# BRD2_1.net
KiCad netlist of a schematic drawn in Altium Designer
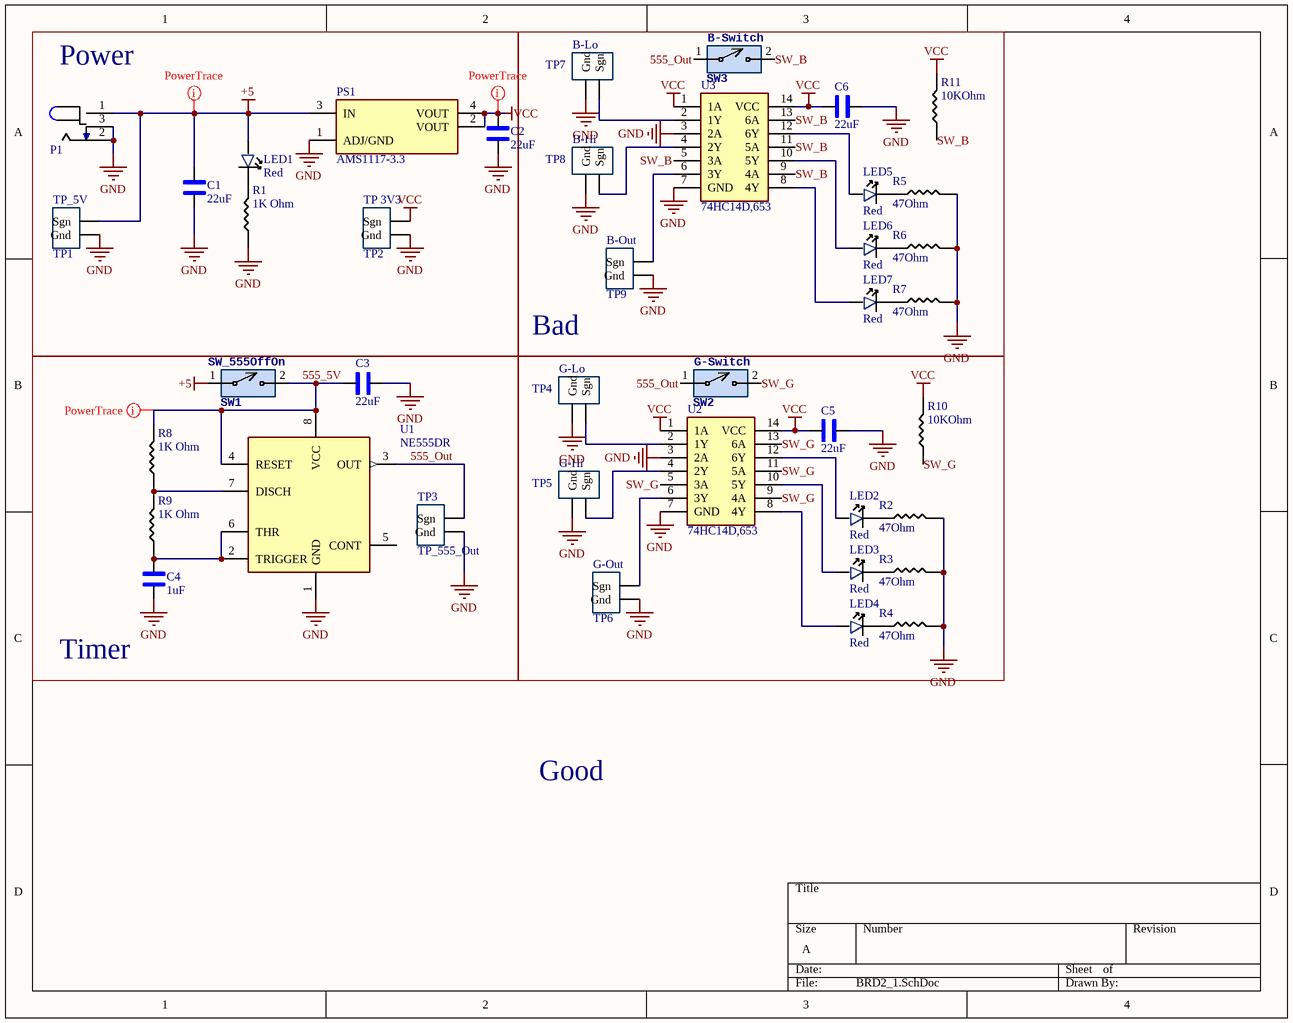
[diagram p0: BRD2_1.SchDoc]

(export (version "E")
  (design (tool "Eeschema 10.0.6"))
  (components
    (comp (ref "C1")
      (value "22uF")
      (footprint "0805_Passive_Capaciitor")
      (description "MULTILAYER CERAMIC CAPACITORS MLCC - SMD/SMT 22UF 25V 0805 ROHS")
      (fields (field (name "MFR PART #") "CL21A226MAQNNNE") (field (name "LCSC PART#") "C45783"))
      (libsource (lib "ECEN5730Lib_JLC_2021_07") (part "C_22uF_0805"))
    )
    (comp (ref "C2")
      (value "22uF")
      (footprint "0805_Passive_Capaciitor")
      (description "MULTILAYER CERAMIC CAPACITORS MLCC - SMD/SMT 22UF 25V 0805 ROHS")
      (fields (field (name "MFR PART #") "CL21A226MAQNNNE") (field (name "LCSC PART#") "C45783"))
      (libsource (lib "ECEN5730Lib_JLC_2021_08") (part "C_22uF_0805"))
    )
    (comp (ref "C3")
      (value "22uF")
      (footprint "0805_Passive_Capaciitor")
      (description "MULTILAYER CERAMIC CAPACITORS MLCC - SMD/SMT 22UF 25V 0805 ROHS")
      (fields (field (name "MFR PART #") "CL21A226MAQNNNE") (field (name "LCSC PART#") "C45783"))
      (libsource (lib "ECEN5730Lib_JLC_2021_07") (part "C_22uF_0805"))
    )
    (comp (ref "C4")
      (value "1uF")
      (footprint "0402_Passive_Capacitor")
      (description "MULTILAYER CERAMIC CAPACITORS MLCC - SMD/SMT 1UF 25V 0402 ROHS")
      (fields (field (name "MFR PART #") "CL05A105KA5NQNC") (field (name "LCSC PART#") "C52923"))
      (libsource (lib "ECEN5730Lib_JLC_2021_07") (part "C_1uF_0402"))
    )
    (comp (ref "C5")
      (value "22uF")
      (footprint "0805_Passive_Capaciitor")
      (description "MULTILAYER CERAMIC CAPACITORS MLCC - SMD/SMT 22UF 25V 0805 ROHS")
      (fields (field (name "MFR PART #") "CL21A226MAQNNNE") (field (name "LCSC PART#") "C45783"))
      (libsource (lib "ECEN5730Lib_JLC_2021_08") (part "C_22uF_0805"))
    )
    (comp (ref "C6")
      (value "22uF")
      (footprint "0805_Passive_Capaciitor")
      (description "MULTILAYER CERAMIC CAPACITORS MLCC - SMD/SMT 22UF 25V 0805 ROHS")
      (fields (field (name "MFR PART #") "CL21A226MAQNNNE") (field (name "LCSC PART#") "C45783"))
      (libsource (lib "ECEN5730Lib_JLC_2021_08") (part "C_22uF_0805"))
    )
    (comp (ref "LED1")
      (value "Red")
      (footprint "LED_0603")
      (description "LIGHT EMITTING DIODES (LED) RED 520~625NM 90~100MCD@20MA TOP VIEW 0603 ROHS")
      (fields (field (name "MFR PART #") "KT-0603R") (field (name "LCSC PART#") "C2286"))
      (libsource (lib "ECEN5730Lib_JLC_2021_07") (part "LED_RED_0603"))
    )
    (comp (ref "LED2")
      (value "Red")
      (footprint "LED_0603")
      (description "LIGHT EMITTING DIODES (LED) RED 520~625NM 90~100MCD@20MA TOP VIEW 0603 ROHS")
      (fields (field (name "MFR PART #") "KT-0603R") (field (name "LCSC PART#") "C2286"))
      (libsource (lib "ECEN5730Lib_JLC_2021_08") (part "LED_RED_0603"))
    )
    (comp (ref "LED3")
      (value "Red")
      (footprint "LED_0603")
      (description "LIGHT EMITTING DIODES (LED) RED 520~625NM 90~100MCD@20MA TOP VIEW 0603 ROHS")
      (fields (field (name "MFR PART #") "KT-0603R") (field (name "LCSC PART#") "C2286"))
      (libsource (lib "ECEN5730Lib_JLC_2021_08") (part "LED_RED_0603"))
    )
    (comp (ref "LED4")
      (value "Red")
      (footprint "LED_0603")
      (description "LIGHT EMITTING DIODES (LED) RED 520~625NM 90~100MCD@20MA TOP VIEW 0603 ROHS")
      (fields (field (name "MFR PART #") "KT-0603R") (field (name "LCSC PART#") "C2286"))
      (libsource (lib "ECEN5730Lib_JLC_2021_08") (part "LED_RED_0603"))
    )
    (comp (ref "LED5")
      (value "Red")
      (footprint "LED_0603")
      (description "LIGHT EMITTING DIODES (LED) RED 520~625NM 90~100MCD@20MA TOP VIEW 0603 ROHS")
      (fields (field (name "MFR PART #") "KT-0603R") (field (name "LCSC PART#") "C2286"))
      (libsource (lib "ECEN5730Lib_JLC_2021_08") (part "LED_RED_0603"))
    )
    (comp (ref "LED6")
      (value "Red")
      (footprint "LED_0603")
      (description "LIGHT EMITTING DIODES (LED) RED 520~625NM 90~100MCD@20MA TOP VIEW 0603 ROHS")
      (fields (field (name "MFR PART #") "KT-0603R") (field (name "LCSC PART#") "C2286"))
      (libsource (lib "ECEN5730Lib_JLC_2021_08") (part "LED_RED_0603"))
    )
    (comp (ref "LED7")
      (value "Red")
      (footprint "LED_0603")
      (description "LIGHT EMITTING DIODES (LED) RED 520~625NM 90~100MCD@20MA TOP VIEW 0603 ROHS")
      (fields (field (name "MFR PART #") "KT-0603R") (field (name "LCSC PART#") "C2286"))
      (libsource (lib "ECEN5730Lib_JLC_2021_08") (part "LED_RED_0603"))
    )
    (comp (ref "P1")
      (value "Power Jack")
      (footprint "Power_Jack")
      (description "Power Barrel Connector Jack 2.10mm ID (0.083\"), 5.50mm OD (0.217\") Through Hole, Right Angle")
      (fields (field (name "DIGIKEY PART") "CP-102A-ND") (field (name "LCSC PART#") "C136744"))
      (libsource (lib "ECEN5730Lib_JLC_2021_07") (part "P_Power Jack"))
    )
    (comp (ref "PS1")
      (value "AMS1117-3.3")
      (footprint "LDO")
      (description "LOW DROPOUT REGULATORS(LDO) POSITIVE FIXED 1.3V @ 800MA 15V 3.3V 1A SOT-223 ROHS")
      (fields (field (name "LCSC PART#") "C6186"))
      (libsource (lib "ECEN5730Lib_JLC_2021_08") (part "PS_AMS_LDO_3v3"))
    )
    (comp (ref "R1")
      (value "1K Ohm")
      (footprint "0402_Passive_Resistor")
      (description "1 kOhms chip resistor SURFACE MOUNT 1KOHMS ±1% 1/16W 0402 ROHS")
      (fields (field (name "MFR PART #") "0402WGF1001TCE") (field (name "LCSC PART#") "C11702"))
      (libsource (lib "ECEN5730Lib_JLC_2021_07") (part "R_1K_0402"))
    )
    (comp (ref "R2")
      (value "47Ohm")
      (footprint "0402_Passive_Resistor")
      (description "CHIP RESISTOR - SURFACE MOUNT 47OHMS ±1% 1/16W 0402 ROHS")
      (fields (field (name "MFR PART #") "0402WGF470JTCE") (field (name "LCSC PART#") "C25118"))
      (libsource (lib "ECEN5730Lib_JLC_2021_08") (part "R_47Ohm_0402"))
    )
    (comp (ref "R3")
      (value "47Ohm")
      (footprint "0402_Passive_Resistor")
      (description "CHIP RESISTOR - SURFACE MOUNT 47OHMS ±1% 1/16W 0402 ROHS")
      (fields (field (name "MFR PART #") "0402WGF470JTCE") (field (name "LCSC PART#") "C25118"))
      (libsource (lib "ECEN5730Lib_JLC_2021_08") (part "R_47Ohm_0402"))
    )
    (comp (ref "R4")
      (value "47Ohm")
      (footprint "0402_Passive_Resistor")
      (description "CHIP RESISTOR - SURFACE MOUNT 47OHMS ±1% 1/16W 0402 ROHS")
      (fields (field (name "MFR PART #") "0402WGF470JTCE") (field (name "LCSC PART#") "C25118"))
      (libsource (lib "ECEN5730Lib_JLC_2021_08") (part "R_47Ohm_0402"))
    )
    (comp (ref "R5")
      (value "47Ohm")
      (footprint "0402_Passive_Resistor")
      (description "CHIP RESISTOR - SURFACE MOUNT 47OHMS ±1% 1/16W 0402 ROHS")
      (fields (field (name "MFR PART #") "0402WGF470JTCE") (field (name "LCSC PART#") "C25118"))
      (libsource (lib "ECEN5730Lib_JLC_2021_08") (part "R_47Ohm_0402"))
    )
    (comp (ref "R6")
      (value "47Ohm")
      (footprint "0402_Passive_Resistor")
      (description "CHIP RESISTOR - SURFACE MOUNT 47OHMS ±1% 1/16W 0402 ROHS")
      (fields (field (name "MFR PART #") "0402WGF470JTCE") (field (name "LCSC PART#") "C25118"))
      (libsource (lib "ECEN5730Lib_JLC_2021_08") (part "R_47Ohm_0402"))
    )
    (comp (ref "R7")
      (value "47Ohm")
      (footprint "0402_Passive_Resistor")
      (description "CHIP RESISTOR - SURFACE MOUNT 47OHMS ±1% 1/16W 0402 ROHS")
      (fields (field (name "MFR PART #") "0402WGF470JTCE") (field (name "LCSC PART#") "C25118"))
      (libsource (lib "ECEN5730Lib_JLC_2021_08") (part "R_47Ohm_0402"))
    )
    (comp (ref "R8")
      (value "1K Ohm")
      (footprint "0402_Passive_Resistor")
      (description "1 kOhms chip resistor SURFACE MOUNT 1KOHMS ±1% 1/16W 0402 ROHS")
      (fields (field (name "MFR PART #") "0402WGF1001TCE") (field (name "LCSC PART#") "C11702"))
      (libsource (lib "ECEN5730Lib_JLC_2021_07") (part "R_1K_0402"))
    )
    (comp (ref "R9")
      (value "1K Ohm")
      (footprint "0402_Passive_Resistor")
      (description "1 kOhms chip resistor SURFACE MOUNT 1KOHMS ±1% 1/16W 0402 ROHS")
      (fields (field (name "MFR PART #") "0402WGF1001TCE") (field (name "LCSC PART#") "C11702"))
      (libsource (lib "ECEN5730Lib_JLC_2021_07") (part "R_1K_0402"))
    )
    (comp (ref "R10")
      (value "10KOhm")
      (footprint "0402_Passive_Resistor")
      (description "CHIP RESISTOR - SURFACE MOUNT 10KOHMS ±1% 1/16W 0402 ROHS")
      (fields (field (name "MFR PART #") "0402WGF1002TCE") (field (name "LCSC PART#") "C25744"))
      (libsource (lib "ECEN5730Lib_JLC_2021_08") (part "R_10KOhm_0402"))
    )
    (comp (ref "R11")
      (value "10KOhm")
      (footprint "0402_Passive_Resistor")
      (description "CHIP RESISTOR - SURFACE MOUNT 10KOHMS ±1% 1/16W 0402 ROHS")
      (fields (field (name "MFR PART #") "0402WGF1002TCE") (field (name "LCSC PART#") "C25744"))
      (libsource (lib "ECEN5730Lib_JLC_2021_08") (part "R_10KOhm_0402"))
    )
    (comp (ref "SW1")
      (value "SW_555OffOn")
      (footprint "2Pin-Header-Conn")
      (description "2Pin Header")
      (fields (field (name "LCSC PART#") "C124375"))
      (libsource (lib "ECEN5730Lib_JLC_2021_07") (part "SW_2Pin_100mil_Switch"))
    )
    (comp (ref "SW2")
      (value "G-Switch")
      (footprint "2Pin-Header-Conn")
      (description "2Pin Header")
      (fields (field (name "LCSC PART#") "C124375"))
      (libsource (lib "ECEN5730Lib_JLC_2021_08") (part "SW_2Pin_100mil_Switch"))
    )
    (comp (ref "SW3")
      (value "B-Switch")
      (footprint "2Pin-Header-Conn")
      (description "2Pin Header")
      (fields (field (name "LCSC PART#") "C124375"))
      (libsource (lib "ECEN5730Lib_JLC_2021_08") (part "SW_2Pin_100mil_Switch"))
    )
    (comp (ref "TP1")
      (value "TP_5V")
      (footprint "TP10x_Probe")
      (description "Test Point 300 mil centers")
      (libsource (lib "ECEN5730Lib_Manual_2021_07") (part "TP_10x_Probe"))
    )
    (comp (ref "TP2")
      (value "TP 3V3")
      (footprint "TP10x_Probe")
      (description "Test Point 300 mil centers")
      (libsource (lib "ECEN5730Lib_Manual_2021_08") (part "TP_10x_Probe"))
    )
    (comp (ref "TP3")
      (value "TP_555_Out")
      (footprint "TP10x_Probe")
      (description "Test Point 300 mil centers")
      (libsource (lib "ECEN5730Lib_Manual_2021_07") (part "TP_10x_Probe"))
    )
    (comp (ref "TP4")
      (value "G-Lo")
      (footprint "TP10x_Probe")
      (description "Test Point 300 mil centers")
      (libsource (lib "") (part "TP_10x_Probe_1"))
    )
    (comp (ref "TP5")
      (value "G-Hi")
      (footprint "TP10x_Probe")
      (description "Test Point 300 mil centers")
      (libsource (lib "") (part "TP_10x_Probe_1"))
    )
    (comp (ref "TP6")
      (value "G-Out")
      (footprint "TP10x_Probe")
      (description "Test Point 300 mil centers")
      (libsource (lib "ECEN5730Lib_Manual_2021_08") (part "TP_10x_Probe"))
    )
    (comp (ref "TP7")
      (value "B-Lo")
      (footprint "TP10x_Probe")
      (description "Test Point 300 mil centers")
      (libsource (lib "") (part "TP_10x_Probe_1"))
    )
    (comp (ref "TP8")
      (value "B-Hi")
      (footprint "TP10x_Probe")
      (description "Test Point 300 mil centers")
      (libsource (lib "") (part "TP_10x_Probe_1"))
    )
    (comp (ref "TP9")
      (value "B-Out")
      (footprint "TP10x_Probe")
      (description "Test Point 300 mil centers")
      (libsource (lib "ECEN5730Lib_Manual_2021_08") (part "TP_10x_Probe"))
    )
    (comp (ref "U1")
      (value "NE555DR")
      (footprint "TS555IDTTR")
      (description "555 Timer SOIC-8_150MIL ROHS 150ns Rise Time")
      (fields (field (name "LCSC PART#") "C7593"))
      (libsource (lib "ECEN5730Lib_JLC_2021_08") (part "U_555_Slow"))
    )
    (comp (ref "U2")
      (value "74HC14D,653")
      (footprint "HEX_74AC14")
      (description "Inverter IC 6 Channel Schmitt Trigger 14-SOIC")
      (fields (field (name "LCSC PART#") "C5605"))
      (libsource (lib "ECEN5730Lib_JLC_2021_08") (part "U_7414_HC_Hex"))
    )
    (comp (ref "U3")
      (value "74HC14D,653")
      (footprint "HEX_74AC14")
      (description "Inverter IC 6 Channel Schmitt Trigger 14-SOIC")
      (fields (field (name "LCSC PART#") "C5605"))
      (libsource (lib "ECEN5730Lib_JLC_2021_08") (part "U_7414_HC_Hex"))
    )
  )
  (nets
    (net (code "1") (name "+5") (class "Default")
      (node (ref "C1") (pin "2") (pinfunction "2_2") (pintype "passive"))
      (node (ref "LED1") (pin "1") (pinfunction "1_1") (pintype "passive"))
      (node (ref "P1") (pin "1") (pinfunction "1_1") (pintype "power_in"))
      (node (ref "PS1") (pin "3") (pinfunction "IN_3") (pintype "power_in"))
      (node (ref "SW1") (pin "1") (pinfunction "1_1") (pintype "passive"))
      (node (ref "TP1") (pin "1") (pinfunction "Sgn_1") (pintype "passive"))
    )
    (net (code "2") (name "/555_5V") (class "Default")
      (node (ref "C3") (pin "1") (pinfunction "1_1") (pintype "passive"))
      (node (ref "R8") (pin "2") (pinfunction "2_2") (pintype "passive"))
      (node (ref "SW1") (pin "2") (pinfunction "2_2") (pintype "passive"))
      (node (ref "U1") (pin "4") (pinfunction "RESET_4") (pintype "passive"))
      (node (ref "U1") (pin "8") (pinfunction "VCC_8") (pintype "power_in"))
    )
    (net (code "3") (name "/555_Out") (class "Default")
      (node (ref "SW2") (pin "1") (pinfunction "1_1") (pintype "passive"))
      (node (ref "SW3") (pin "1") (pinfunction "1_1") (pintype "passive"))
      (node (ref "TP3") (pin "1") (pinfunction "Sgn_1") (pintype "passive"))
      (node (ref "U1") (pin "3") (pinfunction "OUT_3") (pintype "output"))
    )
    (net (code "4") (name "/SW_B") (class "Default")
      (node (ref "R11") (pin "1") (pinfunction "1_1") (pintype "passive"))
      (node (ref "SW3") (pin "2") (pinfunction "2_2") (pintype "passive"))
      (node (ref "U3") (pin "11") (pinfunction "5A_11") (pintype "passive"))
      (node (ref "U3") (pin "13") (pinfunction "6A_13") (pintype "passive"))
      (node (ref "U3") (pin "5") (pinfunction "3A_5") (pintype "passive"))
      (node (ref "U3") (pin "9") (pinfunction "4A_9") (pintype "passive"))
    )
    (net (code "5") (name "/SW_G") (class "Default")
      (node (ref "R10") (pin "1") (pinfunction "1_1") (pintype "passive"))
      (node (ref "SW2") (pin "2") (pinfunction "2_2") (pintype "passive"))
      (node (ref "U2") (pin "11") (pinfunction "5A_11") (pintype "passive"))
      (node (ref "U2") (pin "13") (pinfunction "6A_13") (pintype "passive"))
      (node (ref "U2") (pin "5") (pinfunction "3A_5") (pintype "passive"))
      (node (ref "U2") (pin "9") (pinfunction "4A_9") (pintype "passive"))
    )
    (net (code "6") (name "GND") (class "Default")
      (node (ref "C1") (pin "1") (pinfunction "1_1") (pintype "passive"))
      (node (ref "C2") (pin "1") (pinfunction "1_1") (pintype "passive"))
      (node (ref "C3") (pin "2") (pinfunction "2_2") (pintype "passive"))
      (node (ref "C4") (pin "2") (pinfunction "2_2") (pintype "passive"))
      (node (ref "C5") (pin "2") (pinfunction "2_2") (pintype "passive"))
      (node (ref "C6") (pin "2") (pinfunction "2_2") (pintype "passive"))
      (node (ref "P1") (pin "2") (pinfunction "2_2") (pintype "power_in"))
      (node (ref "P1") (pin "3") (pinfunction "3_3") (pintype "power_in"))
      (node (ref "PS1") (pin "1") (pinfunction "ADJ/GND_1") (pintype "passive"))
      (node (ref "R1") (pin "1") (pinfunction "1_1") (pintype "passive"))
      (node (ref "R2") (pin "2") (pinfunction "2_2") (pintype "passive"))
      (node (ref "R3") (pin "2") (pinfunction "2_2") (pintype "passive"))
      (node (ref "R4") (pin "2") (pinfunction "2_2") (pintype "passive"))
      (node (ref "R5") (pin "2") (pinfunction "2_2") (pintype "passive"))
      (node (ref "R6") (pin "2") (pinfunction "2_2") (pintype "passive"))
      (node (ref "R7") (pin "2") (pinfunction "2_2") (pintype "passive"))
      (node (ref "TP1") (pin "2") (pinfunction "Gnd_2") (pintype "passive"))
      (node (ref "TP2") (pin "2") (pinfunction "Gnd_2") (pintype "passive"))
      (node (ref "TP3") (pin "2") (pinfunction "Gnd_2") (pintype "passive"))
      (node (ref "TP4") (pin "2") (pinfunction "Gnd_2") (pintype "passive"))
      (node (ref "TP5") (pin "2") (pinfunction "Gnd_2") (pintype "passive"))
      (node (ref "TP6") (pin "2") (pinfunction "Gnd_2") (pintype "passive"))
      (node (ref "TP7") (pin "2") (pinfunction "Gnd_2") (pintype "passive"))
      (node (ref "TP8") (pin "2") (pinfunction "Gnd_2") (pintype "passive"))
      (node (ref "TP9") (pin "2") (pinfunction "Gnd_2") (pintype "passive"))
      (node (ref "U1") (pin "1") (pinfunction "GND_1") (pintype "power_in"))
      (node (ref "U2") (pin "3") (pinfunction "2A_3") (pintype "passive"))
      (node (ref "U2") (pin "7") (pinfunction "GND_7") (pintype "passive"))
      (node (ref "U3") (pin "3") (pinfunction "2A_3") (pintype "passive"))
      (node (ref "U3") (pin "7") (pinfunction "GND_7") (pintype "passive"))
    )
    (net (code "7") (name "Net-(LED1-Pad2)") (class "Default")
      (node (ref "LED1") (pin "2") (pinfunction "2_2") (pintype "passive"))
      (node (ref "R1") (pin "2") (pinfunction "2_2") (pintype "passive"))
    )
    (net (code "8") (name "Net-(LED2-Pad2)") (class "Default")
      (node (ref "LED2") (pin "2") (pinfunction "2_2") (pintype "passive"))
      (node (ref "R2") (pin "1") (pinfunction "1_1") (pintype "passive"))
    )
    (net (code "9") (name "Net-(LED3-Pad2)") (class "Default")
      (node (ref "LED3") (pin "2") (pinfunction "2_2") (pintype "passive"))
      (node (ref "R3") (pin "1") (pinfunction "1_1") (pintype "passive"))
    )
    (net (code "10") (name "Net-(LED4-Pad2)") (class "Default")
      (node (ref "LED4") (pin "2") (pinfunction "2_2") (pintype "passive"))
      (node (ref "R4") (pin "1") (pinfunction "1_1") (pintype "passive"))
    )
    (net (code "11") (name "Net-(LED5-Pad2)") (class "Default")
      (node (ref "LED5") (pin "2") (pinfunction "2_2") (pintype "passive"))
      (node (ref "R5") (pin "1") (pinfunction "1_1") (pintype "passive"))
    )
    (net (code "12") (name "Net-(LED6-Pad2)") (class "Default")
      (node (ref "LED6") (pin "2") (pinfunction "2_2") (pintype "passive"))
      (node (ref "R6") (pin "1") (pinfunction "1_1") (pintype "passive"))
    )
    (net (code "13") (name "Net-(LED7-Pad2)") (class "Default")
      (node (ref "LED7") (pin "2") (pinfunction "2_2") (pintype "passive"))
      (node (ref "R7") (pin "1") (pinfunction "1_1") (pintype "passive"))
    )
    (net (code "14") (name "Net-(TP4-Sgn)") (class "Default")
      (node (ref "TP4") (pin "1") (pinfunction "Sgn_1") (pintype "passive"))
      (node (ref "U2") (pin "2") (pinfunction "1Y_2") (pintype "passive"))
    )
    (net (code "15") (name "Net-(TP5-Sgn)") (class "Default")
      (node (ref "TP5") (pin "1") (pinfunction "Sgn_1") (pintype "passive"))
      (node (ref "U2") (pin "4") (pinfunction "2Y_4") (pintype "passive"))
    )
    (net (code "16") (name "Net-(TP6-Sgn)") (class "Default")
      (node (ref "TP6") (pin "1") (pinfunction "Sgn_1") (pintype "passive"))
      (node (ref "U2") (pin "6") (pinfunction "3Y_6") (pintype "passive"))
    )
    (net (code "17") (name "Net-(TP7-Sgn)") (class "Default")
      (node (ref "TP7") (pin "1") (pinfunction "Sgn_1") (pintype "passive"))
      (node (ref "U3") (pin "2") (pinfunction "1Y_2") (pintype "passive"))
    )
    (net (code "18") (name "Net-(TP8-Sgn)") (class "Default")
      (node (ref "TP8") (pin "1") (pinfunction "Sgn_1") (pintype "passive"))
      (node (ref "U3") (pin "4") (pinfunction "2Y_4") (pintype "passive"))
    )
    (net (code "19") (name "Net-(TP9-Sgn)") (class "Default")
      (node (ref "TP9") (pin "1") (pinfunction "Sgn_1") (pintype "passive"))
      (node (ref "U3") (pin "6") (pinfunction "3Y_6") (pintype "passive"))
    )
    (net (code "20") (name "Net-(U1-DISCH)") (class "Default")
      (node (ref "R8") (pin "1") (pinfunction "1_1") (pintype "passive"))
      (node (ref "R9") (pin "2") (pinfunction "2_2") (pintype "passive"))
      (node (ref "U1") (pin "7") (pinfunction "DISCH_7") (pintype "passive"))
    )
    (net (code "21") (name "Net-(U1-THR)") (class "Default")
      (node (ref "C4") (pin "1") (pinfunction "1_1") (pintype "passive"))
      (node (ref "R9") (pin "1") (pinfunction "1_1") (pintype "passive"))
      (node (ref "U1") (pin "2") (pinfunction "TRIGGER_2") (pintype "passive"))
      (node (ref "U1") (pin "6") (pinfunction "THR_6") (pintype "passive"))
    )
    (net (code "22") (name "Net-(U2-4Y)") (class "Default")
      (node (ref "LED4") (pin "1") (pinfunction "1_1") (pintype "passive"))
      (node (ref "U2") (pin "8") (pinfunction "4Y_8") (pintype "passive"))
    )
    (net (code "23") (name "Net-(U2-5Y)") (class "Default")
      (node (ref "LED3") (pin "1") (pinfunction "1_1") (pintype "passive"))
      (node (ref "U2") (pin "10") (pinfunction "5Y_10") (pintype "passive"))
    )
    (net (code "24") (name "Net-(U2-6Y)") (class "Default")
      (node (ref "LED2") (pin "1") (pinfunction "1_1") (pintype "passive"))
      (node (ref "U2") (pin "12") (pinfunction "6Y_12") (pintype "passive"))
    )
    (net (code "25") (name "Net-(U3-4Y)") (class "Default")
      (node (ref "LED7") (pin "1") (pinfunction "1_1") (pintype "passive"))
      (node (ref "U3") (pin "8") (pinfunction "4Y_8") (pintype "passive"))
    )
    (net (code "26") (name "Net-(U3-5Y)") (class "Default")
      (node (ref "LED6") (pin "1") (pinfunction "1_1") (pintype "passive"))
      (node (ref "U3") (pin "10") (pinfunction "5Y_10") (pintype "passive"))
    )
    (net (code "27") (name "Net-(U3-6Y)") (class "Default")
      (node (ref "LED5") (pin "1") (pinfunction "1_1") (pintype "passive"))
      (node (ref "U3") (pin "12") (pinfunction "6Y_12") (pintype "passive"))
    )
    (net (code "28") (name "VCC") (class "Default")
      (node (ref "C2") (pin "2") (pinfunction "2_2") (pintype "passive"))
      (node (ref "C5") (pin "1") (pinfunction "1_1") (pintype "passive"))
      (node (ref "C6") (pin "1") (pinfunction "1_1") (pintype "passive"))
      (node (ref "PS1") (pin "2") (pinfunction "VOUT_2") (pintype "power_in"))
      (node (ref "PS1") (pin "4") (pinfunction "VOUT_4") (pintype "power_in"))
      (node (ref "R10") (pin "2") (pinfunction "2_2") (pintype "passive"))
      (node (ref "R11") (pin "2") (pinfunction "2_2") (pintype "passive"))
      (node (ref "TP2") (pin "1") (pinfunction "Sgn_1") (pintype "passive"))
      (node (ref "U2") (pin "1") (pinfunction "1A_1") (pintype "passive"))
      (node (ref "U2") (pin "14") (pinfunction "VCC_14") (pintype "passive"))
      (node (ref "U3") (pin "1") (pinfunction "1A_1") (pintype "passive"))
      (node (ref "U3") (pin "14") (pinfunction "VCC_14") (pintype "passive"))
    )
    (net (code "29") (name "unconnected-(U1-CONT-Pad5)") (class "Default")
      (node (ref "U1") (pin "5") (pinfunction "CONT_5") (pintype "passive"))
    )
  )
)
